# DDR3_SODIMM_SPD_Breakout.net
KiCad netlist of a schematic drawn in Altium Designer
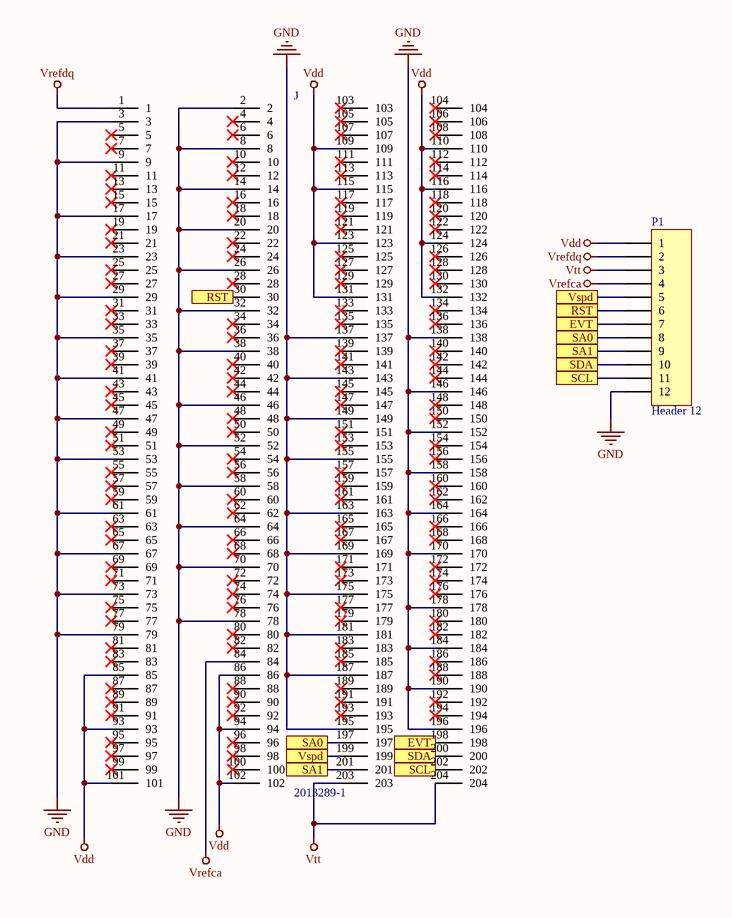
[diagram p0: DDR3 SODIMM SPD Breakout.SchDoc]

(export (version "E")
  (design (tool "Eeschema 10.0.6"))
  (components
    (comp (ref "J")
      (value "2013289-1")
      (footprint "2020-09-26_17-27-19:TE_2013289-1")
      (description "204 Position 0.6 mm Pitch Right Angle Surface Mount Socket DIMM Connector")
      (fields (field (name "DIGI-KEY_PART_NUMBER") "A115021-ND") (field (name "MF") "TE Connectivity"))
      (libsource (lib "2020-09-26_17-27-19") (part "2013289-1"))
    )
    (comp (ref "P1")
      (value "Header 12")
      (footprint "HDR1X12")
      (description "Header, 12-Pin")
      (fields (field (name "PUBLISHER") "Altium Limited"))
      (libsource (lib "Miscellaneous Connectors") (part "Header 12"))
    )
  )
  (nets
    (net (code "1") (name "/EVT") (class "Default")
      (node (ref "J") (pin "198") (pinfunction "198_198") (pintype "passive"))
      (node (ref "P1") (pin "7") (pinfunction "7_7") (pintype "passive"))
    )
    (net (code "2") (name "/RST") (class "Default")
      (node (ref "J") (pin "30") (pinfunction "30_30") (pintype "passive"))
      (node (ref "P1") (pin "6") (pinfunction "6_6") (pintype "passive"))
    )
    (net (code "3") (name "/SA0") (class "Default")
      (node (ref "J") (pin "197") (pinfunction "197_197") (pintype "passive"))
      (node (ref "P1") (pin "8") (pinfunction "8_8") (pintype "passive"))
    )
    (net (code "4") (name "/SA1") (class "Default")
      (node (ref "J") (pin "201") (pinfunction "201_201") (pintype "passive"))
      (node (ref "P1") (pin "9") (pinfunction "9_9") (pintype "passive"))
    )
    (net (code "5") (name "/SCL") (class "Default")
      (node (ref "J") (pin "202") (pinfunction "202_202") (pintype "passive"))
      (node (ref "P1") (pin "11") (pinfunction "11_11") (pintype "passive"))
    )
    (net (code "6") (name "/SDA") (class "Default")
      (node (ref "J") (pin "200") (pinfunction "200_200") (pintype "passive"))
      (node (ref "P1") (pin "10") (pinfunction "10_10") (pintype "passive"))
    )
    (net (code "7") (name "/Vspd") (class "Default")
      (node (ref "J") (pin "199") (pinfunction "199_199") (pintype "passive"))
      (node (ref "P1") (pin "5") (pinfunction "5_5") (pintype "passive"))
    )
    (net (code "8") (name "GND") (class "Default")
      (node (ref "J") (pin "137") (pinfunction "137_137") (pintype "passive"))
      (node (ref "J") (pin "138") (pinfunction "138_138") (pintype "passive"))
      (node (ref "J") (pin "14") (pinfunction "14_14") (pintype "passive"))
      (node (ref "J") (pin "143") (pinfunction "143_143") (pintype "passive"))
      (node (ref "J") (pin "146") (pinfunction "146_146") (pintype "passive"))
      (node (ref "J") (pin "149") (pinfunction "149_149") (pintype "passive"))
      (node (ref "J") (pin "152") (pinfunction "152_152") (pintype "passive"))
      (node (ref "J") (pin "155") (pinfunction "155_155") (pintype "passive"))
      (node (ref "J") (pin "158") (pinfunction "158_158") (pintype "passive"))
      (node (ref "J") (pin "163") (pinfunction "163_163") (pintype "passive"))
      (node (ref "J") (pin "164") (pinfunction "164_164") (pintype "passive"))
      (node (ref "J") (pin "169") (pinfunction "169_169") (pintype "passive"))
      (node (ref "J") (pin "17") (pinfunction "17_17") (pintype "passive"))
      (node (ref "J") (pin "170") (pinfunction "170_170") (pintype "passive"))
      (node (ref "J") (pin "175") (pinfunction "175_175") (pintype "passive"))
      (node (ref "J") (pin "178") (pinfunction "178_178") (pintype "passive"))
      (node (ref "J") (pin "181") (pinfunction "181_181") (pintype "passive"))
      (node (ref "J") (pin "184") (pinfunction "184_184") (pintype "passive"))
      (node (ref "J") (pin "187") (pinfunction "187_187") (pintype "passive"))
      (node (ref "J") (pin "190") (pinfunction "190_190") (pintype "passive"))
      (node (ref "J") (pin "195") (pinfunction "195_195") (pintype "passive"))
      (node (ref "J") (pin "196") (pinfunction "196_196") (pintype "passive"))
      (node (ref "J") (pin "2") (pinfunction "2_2") (pintype "passive"))
      (node (ref "J") (pin "20") (pinfunction "20_20") (pintype "passive"))
      (node (ref "J") (pin "23") (pinfunction "23_23") (pintype "passive"))
      (node (ref "J") (pin "26") (pinfunction "26_26") (pintype "passive"))
      (node (ref "J") (pin "29") (pinfunction "29_29") (pintype "passive"))
      (node (ref "J") (pin "3") (pinfunction "3_3") (pintype "passive"))
      (node (ref "J") (pin "32") (pinfunction "32_32") (pintype "passive"))
      (node (ref "J") (pin "35") (pinfunction "35_35") (pintype "passive"))
      (node (ref "J") (pin "38") (pinfunction "38_38") (pintype "passive"))
      (node (ref "J") (pin "41") (pinfunction "41_41") (pintype "passive"))
      (node (ref "J") (pin "46") (pinfunction "46_46") (pintype "passive"))
      (node (ref "J") (pin "47") (pinfunction "47_47") (pintype "passive"))
      (node (ref "J") (pin "52") (pinfunction "52_52") (pintype "passive"))
      (node (ref "J") (pin "53") (pinfunction "53_53") (pintype "passive"))
      (node (ref "J") (pin "58") (pinfunction "58_58") (pintype "passive"))
      (node (ref "J") (pin "61") (pinfunction "61_61") (pintype "passive"))
      (node (ref "J") (pin "64") (pinfunction "64_64") (pintype "passive"))
      (node (ref "J") (pin "67") (pinfunction "67_67") (pintype "passive"))
      (node (ref "J") (pin "70") (pinfunction "70_70") (pintype "passive"))
      (node (ref "J") (pin "73") (pinfunction "73_73") (pintype "passive"))
      (node (ref "J") (pin "78") (pinfunction "78_78") (pintype "passive"))
      (node (ref "J") (pin "79") (pinfunction "79_79") (pintype "passive"))
      (node (ref "J") (pin "8") (pinfunction "8_8") (pintype "passive"))
      (node (ref "J") (pin "9") (pinfunction "9_9") (pintype "passive"))
      (node (ref "P1") (pin "12") (pinfunction "12_12") (pintype "passive"))
    )
    (net (code "9") (name "Vdd") (class "Default")
      (node (ref "J") (pin "101") (pinfunction "101_101") (pintype "passive"))
      (node (ref "J") (pin "102") (pinfunction "102_102") (pintype "passive"))
      (node (ref "J") (pin "109") (pinfunction "109_109") (pintype "passive"))
      (node (ref "J") (pin "110") (pinfunction "110_110") (pintype "passive"))
      (node (ref "J") (pin "115") (pinfunction "115_115") (pintype "passive"))
      (node (ref "J") (pin "116") (pinfunction "116_116") (pintype "passive"))
      (node (ref "J") (pin "123") (pinfunction "123_123") (pintype "passive"))
      (node (ref "J") (pin "124") (pinfunction "124_124") (pintype "passive"))
      (node (ref "J") (pin "131") (pinfunction "131_131") (pintype "passive"))
      (node (ref "J") (pin "132") (pinfunction "132_132") (pintype "passive"))
      (node (ref "J") (pin "85") (pinfunction "85_85") (pintype "passive"))
      (node (ref "J") (pin "86") (pinfunction "86_86") (pintype "passive"))
      (node (ref "J") (pin "93") (pinfunction "93_93") (pintype "passive"))
      (node (ref "J") (pin "94") (pinfunction "94_94") (pintype "passive"))
      (node (ref "P1") (pin "1") (pinfunction "1_1") (pintype "passive"))
    )
    (net (code "10") (name "Vrefca") (class "Default")
      (node (ref "J") (pin "84") (pinfunction "84_84") (pintype "passive"))
      (node (ref "P1") (pin "4") (pinfunction "4_4") (pintype "passive"))
    )
    (net (code "11") (name "Vrefdq") (class "Default")
      (node (ref "J") (pin "1") (pinfunction "1_1") (pintype "passive"))
      (node (ref "P1") (pin "2") (pinfunction "2_2") (pintype "passive"))
    )
    (net (code "12") (name "Vtt") (class "Default")
      (node (ref "J") (pin "203") (pinfunction "203_203") (pintype "passive"))
      (node (ref "J") (pin "204") (pinfunction "204_204") (pintype "passive"))
      (node (ref "P1") (pin "3") (pinfunction "3_3") (pintype "passive"))
    )
    (net (code "13") (name "unconnected-(J-Pad4)") (class "Default")
      (node (ref "J") (pin "4") (pinfunction "4_4") (pintype "passive+no_connect"))
    )
    (net (code "14") (name "unconnected-(J-Pad5)") (class "Default")
      (node (ref "J") (pin "5") (pinfunction "5_5") (pintype "passive+no_connect"))
    )
    (net (code "15") (name "unconnected-(J-Pad6)") (class "Default")
      (node (ref "J") (pin "6") (pinfunction "6_6") (pintype "passive+no_connect"))
    )
    (net (code "16") (name "unconnected-(J-Pad7)") (class "Default")
      (node (ref "J") (pin "7") (pinfunction "7_7") (pintype "passive+no_connect"))
    )
    (net (code "17") (name "unconnected-(J-Pad10)") (class "Default")
      (node (ref "J") (pin "10") (pinfunction "10_10") (pintype "passive+no_connect"))
    )
    (net (code "18") (name "unconnected-(J-Pad11)") (class "Default")
      (node (ref "J") (pin "11") (pinfunction "11_11") (pintype "passive+no_connect"))
    )
    (net (code "19") (name "unconnected-(J-Pad12)") (class "Default")
      (node (ref "J") (pin "12") (pinfunction "12_12") (pintype "passive+no_connect"))
    )
    (net (code "20") (name "unconnected-(J-Pad13)") (class "Default")
      (node (ref "J") (pin "13") (pinfunction "13_13") (pintype "passive+no_connect"))
    )
    (net (code "21") (name "unconnected-(J-Pad15)") (class "Default")
      (node (ref "J") (pin "15") (pinfunction "15_15") (pintype "passive+no_connect"))
    )
    (net (code "22") (name "unconnected-(J-Pad16)") (class "Default")
      (node (ref "J") (pin "16") (pinfunction "16_16") (pintype "passive+no_connect"))
    )
    (net (code "23") (name "unconnected-(J-Pad18)") (class "Default")
      (node (ref "J") (pin "18") (pinfunction "18_18") (pintype "passive+no_connect"))
    )
    (net (code "24") (name "unconnected-(J-Pad19)") (class "Default")
      (node (ref "J") (pin "19") (pinfunction "19_19") (pintype "passive+no_connect"))
    )
    (net (code "25") (name "unconnected-(J-Pad21)") (class "Default")
      (node (ref "J") (pin "21") (pinfunction "21_21") (pintype "passive+no_connect"))
    )
    (net (code "26") (name "unconnected-(J-Pad22)") (class "Default")
      (node (ref "J") (pin "22") (pinfunction "22_22") (pintype "passive+no_connect"))
    )
    (net (code "27") (name "unconnected-(J-Pad24)") (class "Default")
      (node (ref "J") (pin "24") (pinfunction "24_24") (pintype "passive+no_connect"))
    )
    (net (code "28") (name "unconnected-(J-Pad25)") (class "Default")
      (node (ref "J") (pin "25") (pinfunction "25_25") (pintype "passive+no_connect"))
    )
    (net (code "29") (name "unconnected-(J-Pad27)") (class "Default")
      (node (ref "J") (pin "27") (pinfunction "27_27") (pintype "passive+no_connect"))
    )
    (net (code "30") (name "unconnected-(J-Pad28)") (class "Default")
      (node (ref "J") (pin "28") (pinfunction "28_28") (pintype "passive+no_connect"))
    )
    (net (code "31") (name "unconnected-(J-Pad31)") (class "Default")
      (node (ref "J") (pin "31") (pinfunction "31_31") (pintype "passive+no_connect"))
    )
    (net (code "32") (name "unconnected-(J-Pad33)") (class "Default")
      (node (ref "J") (pin "33") (pinfunction "33_33") (pintype "passive+no_connect"))
    )
    (net (code "33") (name "unconnected-(J-Pad34)") (class "Default")
      (node (ref "J") (pin "34") (pinfunction "34_34") (pintype "passive+no_connect"))
    )
    (net (code "34") (name "unconnected-(J-Pad36)") (class "Default")
      (node (ref "J") (pin "36") (pinfunction "36_36") (pintype "passive+no_connect"))
    )
    (net (code "35") (name "unconnected-(J-Pad37)") (class "Default")
      (node (ref "J") (pin "37") (pinfunction "37_37") (pintype "passive+no_connect"))
    )
    (net (code "36") (name "unconnected-(J-Pad39)") (class "Default")
      (node (ref "J") (pin "39") (pinfunction "39_39") (pintype "passive+no_connect"))
    )
    (net (code "37") (name "unconnected-(J-Pad40)") (class "Default")
      (node (ref "J") (pin "40") (pinfunction "40_40") (pintype "passive+no_connect"))
    )
    (net (code "38") (name "unconnected-(J-Pad42)") (class "Default")
      (node (ref "J") (pin "42") (pinfunction "42_42") (pintype "passive+no_connect"))
    )
    (net (code "39") (name "unconnected-(J-Pad43)") (class "Default")
      (node (ref "J") (pin "43") (pinfunction "43_43") (pintype "passive+no_connect"))
    )
    (net (code "40") (name "unconnected-(J-Pad44)") (class "Default")
      (node (ref "J") (pin "44") (pinfunction "44_44") (pintype "passive+no_connect"))
    )
    (net (code "41") (name "unconnected-(J-Pad45)") (class "Default")
      (node (ref "J") (pin "45") (pinfunction "45_45") (pintype "passive+no_connect"))
    )
    (net (code "42") (name "unconnected-(J-Pad48)") (class "Default")
      (node (ref "J") (pin "48") (pinfunction "48_48") (pintype "passive+no_connect"))
    )
    (net (code "43") (name "unconnected-(J-Pad49)") (class "Default")
      (node (ref "J") (pin "49") (pinfunction "49_49") (pintype "passive+no_connect"))
    )
    (net (code "44") (name "unconnected-(J-Pad50)") (class "Default")
      (node (ref "J") (pin "50") (pinfunction "50_50") (pintype "passive+no_connect"))
    )
    (net (code "45") (name "unconnected-(J-Pad51)") (class "Default")
      (node (ref "J") (pin "51") (pinfunction "51_51") (pintype "passive+no_connect"))
    )
    (net (code "46") (name "unconnected-(J-Pad54)") (class "Default")
      (node (ref "J") (pin "54") (pinfunction "54_54") (pintype "passive+no_connect"))
    )
    (net (code "47") (name "unconnected-(J-Pad55)") (class "Default")
      (node (ref "J") (pin "55") (pinfunction "55_55") (pintype "passive+no_connect"))
    )
    (net (code "48") (name "unconnected-(J-Pad56)") (class "Default")
      (node (ref "J") (pin "56") (pinfunction "56_56") (pintype "passive+no_connect"))
    )
    (net (code "49") (name "unconnected-(J-Pad57)") (class "Default")
      (node (ref "J") (pin "57") (pinfunction "57_57") (pintype "passive+no_connect"))
    )
    (net (code "50") (name "unconnected-(J-Pad59)") (class "Default")
      (node (ref "J") (pin "59") (pinfunction "59_59") (pintype "passive+no_connect"))
    )
    (net (code "51") (name "unconnected-(J-Pad60)") (class "Default")
      (node (ref "J") (pin "60") (pinfunction "60_60") (pintype "passive+no_connect"))
    )
    (net (code "52") (name "unconnected-(J-Pad62)") (class "Default")
      (node (ref "J") (pin "62") (pinfunction "62_62") (pintype "passive+no_connect"))
    )
    (net (code "53") (name "unconnected-(J-Pad63)") (class "Default")
      (node (ref "J") (pin "63") (pinfunction "63_63") (pintype "passive+no_connect"))
    )
    (net (code "54") (name "unconnected-(J-Pad65)") (class "Default")
      (node (ref "J") (pin "65") (pinfunction "65_65") (pintype "passive+no_connect"))
    )
    (net (code "55") (name "unconnected-(J-Pad66)") (class "Default")
      (node (ref "J") (pin "66") (pinfunction "66_66") (pintype "passive+no_connect"))
    )
    (net (code "56") (name "unconnected-(J-Pad68)") (class "Default")
      (node (ref "J") (pin "68") (pinfunction "68_68") (pintype "passive+no_connect"))
    )
    (net (code "57") (name "unconnected-(J-Pad69)") (class "Default")
      (node (ref "J") (pin "69") (pinfunction "69_69") (pintype "passive+no_connect"))
    )
    (net (code "58") (name "unconnected-(J-Pad71)") (class "Default")
      (node (ref "J") (pin "71") (pinfunction "71_71") (pintype "passive+no_connect"))
    )
    (net (code "59") (name "unconnected-(J-Pad72)") (class "Default")
      (node (ref "J") (pin "72") (pinfunction "72_72") (pintype "passive+no_connect"))
    )
    (net (code "60") (name "unconnected-(J-Pad74)") (class "Default")
      (node (ref "J") (pin "74") (pinfunction "74_74") (pintype "passive+no_connect"))
    )
    (net (code "61") (name "unconnected-(J-Pad75)") (class "Default")
      (node (ref "J") (pin "75") (pinfunction "75_75") (pintype "passive+no_connect"))
    )
    (net (code "62") (name "unconnected-(J-Pad76)") (class "Default")
      (node (ref "J") (pin "76") (pinfunction "76_76") (pintype "passive+no_connect"))
    )
    (net (code "63") (name "unconnected-(J-Pad77)") (class "Default")
      (node (ref "J") (pin "77") (pinfunction "77_77") (pintype "passive+no_connect"))
    )
    (net (code "64") (name "unconnected-(J-Pad80)") (class "Default")
      (node (ref "J") (pin "80") (pinfunction "80_80") (pintype "passive+no_connect"))
    )
    (net (code "65") (name "unconnected-(J-Pad81)") (class "Default")
      (node (ref "J") (pin "81") (pinfunction "81_81") (pintype "passive+no_connect"))
    )
    (net (code "66") (name "unconnected-(J-Pad82)") (class "Default")
      (node (ref "J") (pin "82") (pinfunction "82_82") (pintype "passive+no_connect"))
    )
    (net (code "67") (name "unconnected-(J-Pad83)") (class "Default")
      (node (ref "J") (pin "83") (pinfunction "83_83") (pintype "passive+no_connect"))
    )
    (net (code "68") (name "unconnected-(J-Pad87)") (class "Default")
      (node (ref "J") (pin "87") (pinfunction "87_87") (pintype "passive+no_connect"))
    )
    (net (code "69") (name "unconnected-(J-Pad88)") (class "Default")
      (node (ref "J") (pin "88") (pinfunction "88_88") (pintype "passive+no_connect"))
    )
    (net (code "70") (name "unconnected-(J-Pad89)") (class "Default")
      (node (ref "J") (pin "89") (pinfunction "89_89") (pintype "passive+no_connect"))
    )
    (net (code "71") (name "unconnected-(J-Pad90)") (class "Default")
      (node (ref "J") (pin "90") (pinfunction "90_90") (pintype "passive+no_connect"))
    )
    (net (code "72") (name "unconnected-(J-Pad91)") (class "Default")
      (node (ref "J") (pin "91") (pinfunction "91_91") (pintype "passive+no_connect"))
    )
    (net (code "73") (name "unconnected-(J-Pad92)") (class "Default")
      (node (ref "J") (pin "92") (pinfunction "92_92") (pintype "passive+no_connect"))
    )
    (net (code "74") (name "unconnected-(J-Pad95)") (class "Default")
      (node (ref "J") (pin "95") (pinfunction "95_95") (pintype "passive+no_connect"))
    )
    (net (code "75") (name "unconnected-(J-Pad96)") (class "Default")
      (node (ref "J") (pin "96") (pinfunction "96_96") (pintype "passive+no_connect"))
    )
    (net (code "76") (name "unconnected-(J-Pad97)") (class "Default")
      (node (ref "J") (pin "97") (pinfunction "97_97") (pintype "passive+no_connect"))
    )
    (net (code "77") (name "unconnected-(J-Pad98)") (class "Default")
      (node (ref "J") (pin "98") (pinfunction "98_98") (pintype "passive+no_connect"))
    )
    (net (code "78") (name "unconnected-(J-Pad99)") (class "Default")
      (node (ref "J") (pin "99") (pinfunction "99_99") (pintype "passive+no_connect"))
    )
    (net (code "79") (name "unconnected-(J-Pad100)") (class "Default")
      (node (ref "J") (pin "100") (pinfunction "100_100") (pintype "passive+no_connect"))
    )
    (net (code "80") (name "unconnected-(J-Pad103)") (class "Default")
      (node (ref "J") (pin "103") (pinfunction "103_103") (pintype "passive+no_connect"))
    )
    (net (code "81") (name "unconnected-(J-Pad104)") (class "Default")
      (node (ref "J") (pin "104") (pinfunction "104_104") (pintype "passive+no_connect"))
    )
    (net (code "82") (name "unconnected-(J-Pad105)") (class "Default")
      (node (ref "J") (pin "105") (pinfunction "105_105") (pintype "passive+no_connect"))
    )
    (net (code "83") (name "unconnected-(J-Pad106)") (class "Default")
      (node (ref "J") (pin "106") (pinfunction "106_106") (pintype "passive+no_connect"))
    )
    (net (code "84") (name "unconnected-(J-Pad107)") (class "Default")
      (node (ref "J") (pin "107") (pinfunction "107_107") (pintype "passive+no_connect"))
    )
    (net (code "85") (name "unconnected-(J-Pad108)") (class "Default")
      (node (ref "J") (pin "108") (pinfunction "108_108") (pintype "passive+no_connect"))
    )
    (net (code "86") (name "unconnected-(J-Pad111)") (class "Default")
      (node (ref "J") (pin "111") (pinfunction "111_111") (pintype "passive+no_connect"))
    )
    (net (code "87") (name "unconnected-(J-Pad112)") (class "Default")
      (node (ref "J") (pin "112") (pinfunction "112_112") (pintype "passive+no_connect"))
    )
    (net (code "88") (name "unconnected-(J-Pad113)") (class "Default")
      (node (ref "J") (pin "113") (pinfunction "113_113") (pintype "passive+no_connect"))
    )
    (net (code "89") (name "unconnected-(J-Pad114)") (class "Default")
      (node (ref "J") (pin "114") (pinfunction "114_114") (pintype "passive+no_connect"))
    )
    (net (code "90") (name "unconnected-(J-Pad117)") (class "Default")
      (node (ref "J") (pin "117") (pinfunction "117_117") (pintype "passive+no_connect"))
    )
    (net (code "91") (name "unconnected-(J-Pad118)") (class "Default")
      (node (ref "J") (pin "118") (pinfunction "118_118") (pintype "passive+no_connect"))
    )
    (net (code "92") (name "unconnected-(J-Pad119)") (class "Default")
      (node (ref "J") (pin "119") (pinfunction "119_119") (pintype "passive+no_connect"))
    )
    (net (code "93") (name "unconnected-(J-Pad120)") (class "Default")
      (node (ref "J") (pin "120") (pinfunction "120_120") (pintype "passive+no_connect"))
    )
    (net (code "94") (name "unconnected-(J-Pad121)") (class "Default")
      (node (ref "J") (pin "121") (pinfunction "121_121") (pintype "passive+no_connect"))
    )
    (net (code "95") (name "unconnected-(J-Pad122)") (class "Default")
      (node (ref "J") (pin "122") (pinfunction "122_122") (pintype "passive+no_connect"))
    )
    (net (code "96") (name "unconnected-(J-Pad125)") (class "Default")
      (node (ref "J") (pin "125") (pinfunction "125_125") (pintype "passive+no_connect"))
    )
    (net (code "97") (name "unconnected-(J-Pad126)") (class "Default")
      (node (ref "J") (pin "126") (pinfunction "126_126") (pintype "passive+no_connect"))
    )
    (net (code "98") (name "unconnected-(J-Pad127)") (class "Default")
      (node (ref "J") (pin "127") (pinfunction "127_127") (pintype "passive+no_connect"))
    )
    (net (code "99") (name "unconnected-(J-Pad128)") (class "Default")
      (node (ref "J") (pin "128") (pinfunction "128_128") (pintype "passive+no_connect"))
    )
    (net (code "100") (name "unconnected-(J-Pad129)") (class "Default")
      (node (ref "J") (pin "129") (pinfunction "129_129") (pintype "passive+no_connect"))
    )
    (net (code "101") (name "unconnected-(J-Pad130)") (class "Default")
      (node (ref "J") (pin "130") (pinfunction "130_130") (pintype "passive+no_connect"))
    )
    (net (code "102") (name "unconnected-(J-Pad133)") (class "Default")
      (node (ref "J") (pin "133") (pinfunction "133_133") (pintype "passive+no_connect"))
    )
    (net (code "103") (name "unconnected-(J-Pad134)") (class "Default")
      (node (ref "J") (pin "134") (pinfunction "134_134") (pintype "passive+no_connect"))
    )
    (net (code "104") (name "unconnected-(J-Pad135)") (class "Default")
      (node (ref "J") (pin "135") (pinfunction "135_135") (pintype "passive+no_connect"))
    )
    (net (code "105") (name "unconnected-(J-Pad136)") (class "Default")
      (node (ref "J") (pin "136") (pinfunction "136_136") (pintype "passive+no_connect"))
    )
    (net (code "106") (name "unconnected-(J-Pad139)") (class "Default")
      (node (ref "J") (pin "139") (pinfunction "139_139") (pintype "passive+no_connect"))
    )
    (net (code "107") (name "unconnected-(J-Pad140)") (class "Default")
      (node (ref "J") (pin "140") (pinfunction "140_140") (pintype "passive+no_connect"))
    )
    (net (code "108") (name "unconnected-(J-Pad141)") (class "Default")
      (node (ref "J") (pin "141") (pinfunction "141_141") (pintype "passive+no_connect"))
    )
    (net (code "109") (name "unconnected-(J-Pad142)") (class "Default")
      (node (ref "J") (pin "142") (pinfunction "142_142") (pintype "passive+no_connect"))
    )
    (net (code "110") (name "unconnected-(J-Pad144)") (class "Default")
      (node (ref "J") (pin "144") (pinfunction "144_144") (pintype "passive+no_connect"))
    )
    (net (code "111") (name "unconnected-(J-Pad145)") (class "Default")
      (node (ref "J") (pin "145") (pinfunction "145_145") (pintype "passive+no_connect"))
    )
    (net (code "112") (name "unconnected-(J-Pad147)") (class "Default")
      (node (ref "J") (pin "147") (pinfunction "147_147") (pintype "passive+no_connect"))
    )
    (net (code "113") (name "unconnected-(J-Pad148)") (class "Default")
      (node (ref "J") (pin "148") (pinfunction "148_148") (pintype "passive+no_connect"))
    )
    (net (code "114") (name "unconnected-(J-Pad150)") (class "Default")
      (node (ref "J") (pin "150") (pinfunction "150_150") (pintype "passive+no_connect"))
    )
    (net (code "115") (name "unconnected-(J-Pad151)") (class "Default")
      (node (ref "J") (pin "151") (pinfunction "151_151") (pintype "passive+no_connect"))
    )
    (net (code "116") (name "unconnected-(J-Pad153)") (class "Default")
      (node (ref "J") (pin "153") (pinfunction "153_153") (pintype "passive+no_connect"))
    )
    (net (code "117") (name "unconnected-(J-Pad154)") (class "Default")
      (node (ref "J") (pin "154") (pinfunction "154_154") (pintype "passive+no_connect"))
    )
    (net (code "118") (name "unconnected-(J-Pad156)") (class "Default")
      (node (ref "J") (pin "156") (pinfunction "156_156") (pintype "passive+no_connect"))
    )
    (net (code "119") (name "unconnected-(J-Pad157)") (class "Default")
      (node (ref "J") (pin "157") (pinfunction "157_157") (pintype "passive+no_connect"))
    )
    (net (code "120") (name "unconnected-(J-Pad159)") (class "Default")
      (node (ref "J") (pin "159") (pinfunction "159_159") (pintype "passive+no_connect"))
    )
    (net (code "121") (name "unconnected-(J-Pad160)") (class "Default")
      (node (ref "J") (pin "160") (pinfunction "160_160") (pintype "passive+no_connect"))
    )
    (net (code "122") (name "unconnected-(J-Pad161)") (class "Default")
      (node (ref "J") (pin "161") (pinfunction "161_161") (pintype "passive+no_connect"))
    )
    (net (code "123") (name "unconnected-(J-Pad162)") (class "Default")
      (node (ref "J") (pin "162") (pinfunction "162_162") (pintype "passive+no_connect"))
    )
    (net (code "124") (name "unconnected-(J-Pad165)") (class "Default")
      (node (ref "J") (pin "165") (pinfunction "165_165") (pintype "passive+no_connect"))
    )
    (net (code "125") (name "unconnected-(J-Pad166)") (class "Default")
      (node (ref "J") (pin "166") (pinfunction "166_166") (pintype "passive+no_connect"))
    )
    (net (code "126") (name "unconnected-(J-Pad167)") (class "Default")
      (node (ref "J") (pin "167") (pinfunction "167_167") (pintype "passive+no_connect"))
    )
    (net (code "127") (name "unconnected-(J-Pad168)") (class "Default")
      (node (ref "J") (pin "168") (pinfunction "168_168") (pintype "passive+no_connect"))
    )
    (net (code "128") (name "unconnected-(J-Pad171)") (class "Default")
      (node (ref "J") (pin "171") (pinfunction "171_171") (pintype "passive+no_connect"))
    )
    (net (code "129") (name "unconnected-(J-Pad172)") (class "Default")
      (node (ref "J") (pin "172") (pinfunction "172_172") (pintype "passive+no_connect"))
    )
    (net (code "130") (name "unconnected-(J-Pad173)") (class "Default")
      (node (ref "J") (pin "173") (pinfunction "173_173") (pintype "passive+no_connect"))
    )
    (net (code "131") (name "unconnected-(J-Pad174)") (class "Default")
      (node (ref "J") (pin "174") (pinfunction "174_174") (pintype "passive+no_connect"))
    )
    (net (code "132") (name "unconnected-(J-Pad176)") (class "Default")
      (node (ref "J") (pin "176") (pinfunction "176_176") (pintype "passive+no_connect"))
    )
    (net (code "133") (name "unconnected-(J-Pad177)") (class "Default")
      (node (ref "J") (pin "177") (pinfunction "177_177") (pintype "passive+no_connect"))
    )
    (net (code "134") (name "unconnected-(J-Pad179)") (class "Default")
      (node (ref "J") (pin "179") (pinfunction "179_179") (pintype "passive+no_connect"))
    )
    (net (code "135") (name "unconnected-(J-Pad180)") (class "Default")
      (node (ref "J") (pin "180") (pinfunction "180_180") (pintype "passive+no_connect"))
    )
    (net (code "136") (name "unconnected-(J-Pad182)") (class "Default")
      (node (ref "J") (pin "182") (pinfunction "182_182") (pintype "passive+no_connect"))
    )
    (net (code "137") (name "unconnected-(J-Pad183)") (class "Default")
      (node (ref "J") (pin "183") (pinfunction "183_183") (pintype "passive+no_connect"))
    )
    (net (code "138") (name "unconnected-(J-Pad185)") (class "Default")
      (node (ref "J") (pin "185") (pinfunction "185_185") (pintype "passive+no_connect"))
    )
    (net (code "139") (name "unconnected-(J-Pad186)") (class "Default")
      (node (ref "J") (pin "186") (pinfunction "186_186") (pintype "passive+no_connect"))
    )
    (net (code "140") (name "unconnected-(J-Pad188)") (class "Default")
      (node (ref "J") (pin "188") (pinfunction "188_188") (pintype "passive+no_connect"))
    )
    (net (code "141") (name "unconnected-(J-Pad189)") (class "Default")
      (node (ref "J") (pin "189") (pinfunction "189_189") (pintype "passive+no_connect"))
    )
    (net (code "142") (name "unconnected-(J-Pad191)") (class "Default")
      (node (ref "J") (pin "191") (pinfunction "191_191") (pintype "passive+no_connect"))
    )
    (net (code "143") (name "unconnected-(J-Pad192)") (class "Default")
      (node (ref "J") (pin "192") (pinfunction "192_192") (pintype "passive+no_connect"))
    )
    (net (code "144") (name "unconnected-(J-Pad193)") (class "Default")
      (node (ref "J") (pin "193") (pinfunction "193_193") (pintype "passive+no_connect"))
    )
    (net (code "145") (name "unconnected-(J-Pad194)") (class "Default")
      (node (ref "J") (pin "194") (pinfunction "194_194") (pintype "passive+no_connect"))
    )
  )
)
